# clockWiring.net
KiCad netlist of a schematic drawn in EAGLE
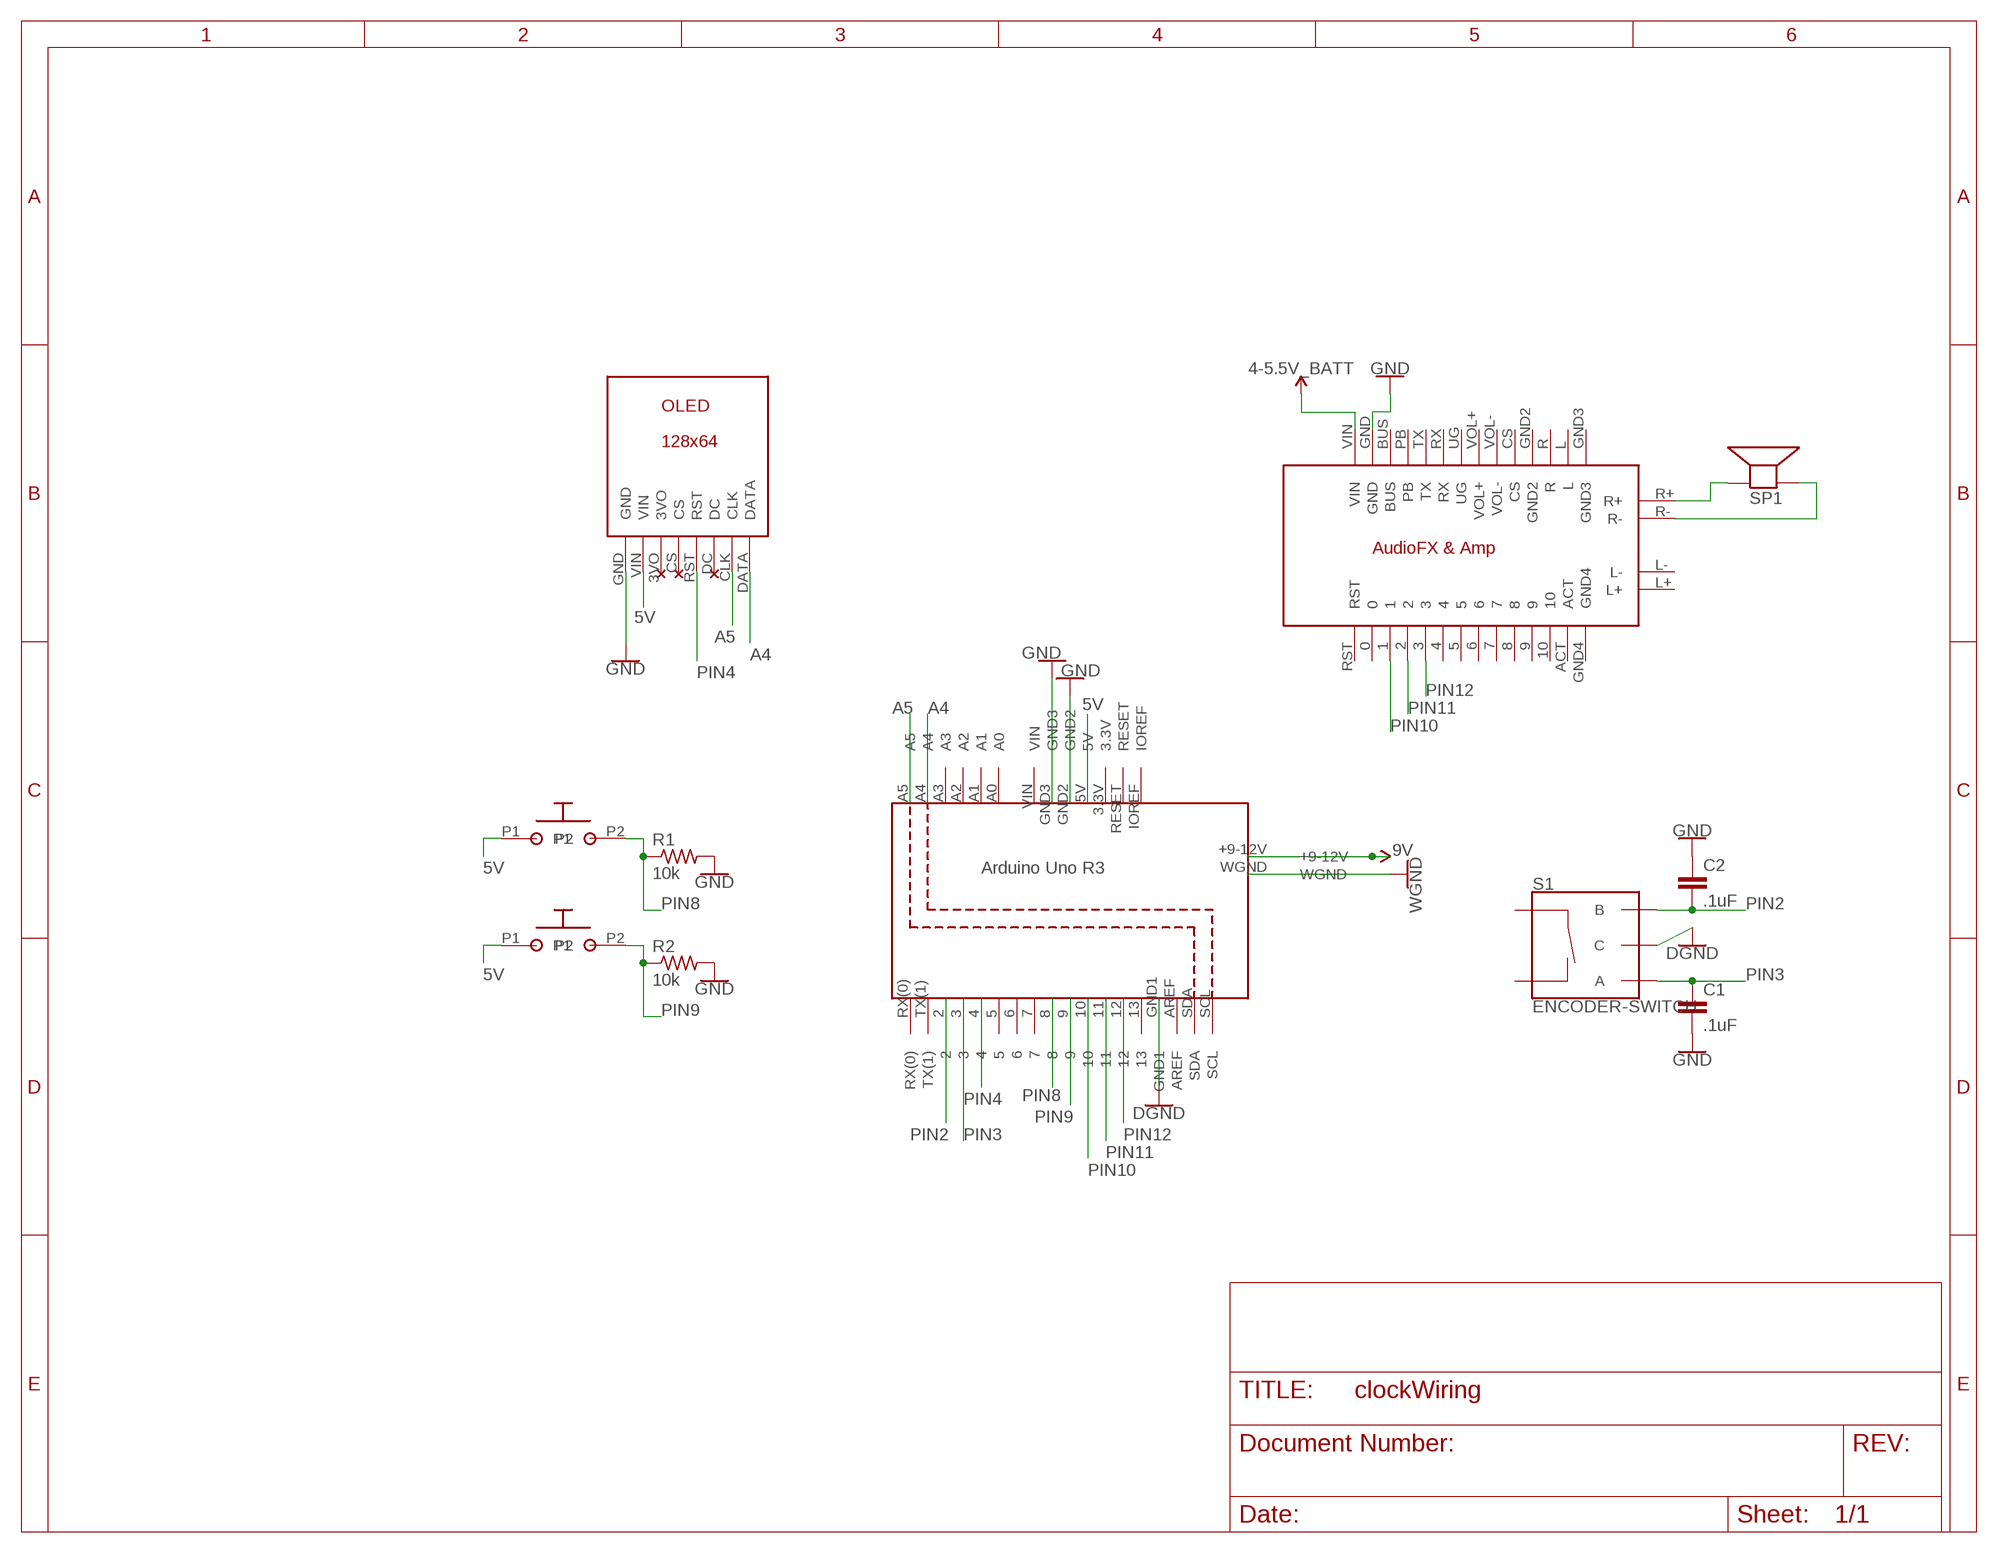
[diagram p0: schematic, sheet 1]

(export (version "E")
  (design (tool "Eeschema 10.0.6"))
  (components
    (comp (ref "C1")
      (value ".1uF")
      (footprint "eagle-import:C2.5-2")
      (libsource (lib "eagle-import") (part "C2.5/2"))
    )
    (comp (ref "C2")
      (value ".1uF")
      (footprint "eagle-import:C2.5-2")
      (libsource (lib "eagle-import") (part "C2.5/2"))
    )
    (comp (ref "R1")
      (value "10k")
      (footprint "eagle-import:0805-THM")
      (libsource (lib "eagle-import") (part "FLIPFLOP-RES"))
    )
    (comp (ref "R2")
      (value "10k")
      (footprint "eagle-import:0805-THM")
      (libsource (lib "eagle-import") (part "FLIPFLOP-RES"))
    )
    (comp (ref "S1")
      (value "ENCODER-SWITCH")
      (footprint "eagle-import:ROTARY_ENC_PLAIN")
      (libsource (lib "eagle-import") (part "ENCODER-SWITCH"))
    )
    (comp (ref "SP1")
      (value "SPEAKER/PS12")
      (footprint "eagle-import:PS12")
      (libsource (lib "eagle-import") (part "SPEAKER/PS12"))
    )
    (comp (ref "U$2")
      (value "OLED_128X64")
      (footprint "eagle-import:OLED_128X64")
      (libsource (lib "eagle-import") (part "OLED_128X64"))
    )
    (comp (ref "U$5")
      (value "AUDIOFX&AMP")
      (footprint "eagle-import:AUDIOFX&AMP")
      (libsource (lib "eagle-import") (part "AUDIOFX&AMP"))
    )
    (comp (ref "U$6")
      (value "ARDUINO_UNO")
      (footprint "eagle-import:ARDUINO_UNO")
      (libsource (lib "eagle-import") (part "ARDUINO_UNO"))
    )
    (comp (ref "U$7")
      (value "TWOPINBUTTON")
      (footprint "eagle-import:TWOPINBUTTON")
      (libsource (lib "eagle-import") (part "TWOPINBUTTON"))
    )
    (comp (ref "U$8")
      (value "TWOPINBUTTON")
      (footprint "eagle-import:TWOPINBUTTON")
      (libsource (lib "eagle-import") (part "TWOPINBUTTON"))
    )
  )
  (nets
    (net (code "1") (name "/5V") (class "Default")
      (node (ref "U$2") (pin "VIN") (pinfunction "VIN_VIN") (pintype "bidirectional"))
      (node (ref "U$6") (pin "5V") (pinfunction "5V_5V") (pintype "bidirectional"))
      (node (ref "U$7") (pin "P1") (pinfunction "P1_P1") (pintype "bidirectional"))
      (node (ref "U$8") (pin "P1") (pinfunction "P1_P1") (pintype "bidirectional"))
    )
    (net (code "2") (name "/A4") (class "Default")
      (node (ref "U$2") (pin "DATA") (pinfunction "DATA_DATA") (pintype "bidirectional"))
      (node (ref "U$6") (pin "A4") (pinfunction "A4_A4") (pintype "bidirectional"))
    )
    (net (code "3") (name "/A5") (class "Default")
      (node (ref "U$2") (pin "CLK") (pinfunction "CLK_CLK") (pintype "bidirectional"))
      (node (ref "U$6") (pin "A5") (pinfunction "A5_A5") (pintype "bidirectional"))
    )
    (net (code "4") (name "/PIN2") (class "Default")
      (node (ref "C2") (pin "2") (pinfunction "2_2") (pintype "passive"))
      (node (ref "S1") (pin "B") (pinfunction "B_B") (pintype "bidirectional"))
      (node (ref "U$6") (pin "2") (pinfunction "2_2") (pintype "bidirectional"))
    )
    (net (code "5") (name "/PIN3") (class "Default")
      (node (ref "C1") (pin "1") (pinfunction "1_1") (pintype "passive"))
      (node (ref "S1") (pin "A") (pinfunction "A_A") (pintype "bidirectional"))
      (node (ref "U$6") (pin "3") (pinfunction "3_3") (pintype "bidirectional"))
    )
    (net (code "6") (name "/PIN4") (class "Default")
      (node (ref "U$2") (pin "RST") (pinfunction "RST_RST") (pintype "bidirectional"))
      (node (ref "U$6") (pin "4") (pinfunction "4_4") (pintype "bidirectional"))
    )
    (net (code "7") (name "/PIN8") (class "Default")
      (node (ref "R1") (pin "1") (pinfunction "1_1") (pintype "passive"))
      (node (ref "U$6") (pin "8") (pinfunction "8_8") (pintype "bidirectional"))
      (node (ref "U$7") (pin "P2") (pinfunction "P2_P2") (pintype "bidirectional"))
    )
    (net (code "8") (name "/PIN9") (class "Default")
      (node (ref "R2") (pin "1") (pinfunction "1_1") (pintype "passive"))
      (node (ref "U$6") (pin "9") (pinfunction "9_9") (pintype "bidirectional"))
      (node (ref "U$8") (pin "P2") (pinfunction "P2_P2") (pintype "bidirectional"))
    )
    (net (code "9") (name "/PIN10") (class "Default")
      (node (ref "U$5") (pin "1") (pinfunction "1_1") (pintype "bidirectional"))
      (node (ref "U$6") (pin "10") (pinfunction "10_10") (pintype "bidirectional"))
    )
    (net (code "10") (name "/PIN11") (class "Default")
      (node (ref "U$5") (pin "2") (pinfunction "2_2") (pintype "bidirectional"))
      (node (ref "U$6") (pin "11") (pinfunction "11_11") (pintype "bidirectional"))
    )
    (net (code "11") (name "/PIN12") (class "Default")
      (node (ref "U$5") (pin "3") (pinfunction "3_3") (pintype "bidirectional"))
      (node (ref "U$6") (pin "12") (pinfunction "12_12") (pintype "bidirectional"))
    )
    (net (code "12") (name "4-5.5V_BATT") (class "Default")
      (node (ref "U$5") (pin "VIN") (pinfunction "VIN_VIN") (pintype "bidirectional"))
    )
    (net (code "13") (name "9V") (class "Default")
      (node (ref "U$6") (pin "+9-12V") (pinfunction "+9-12V_+9-12V") (pintype "bidirectional"))
    )
    (net (code "14") (name "DGND") (class "Default")
      (node (ref "C1") (pin "2") (pinfunction "2_2") (pintype "passive"))
      (node (ref "C2") (pin "1") (pinfunction "1_1") (pintype "passive"))
      (node (ref "R1") (pin "2") (pinfunction "2_2") (pintype "passive"))
      (node (ref "R2") (pin "2") (pinfunction "2_2") (pintype "passive"))
      (node (ref "S1") (pin "C") (pinfunction "C_C") (pintype "bidirectional"))
      (node (ref "U$2") (pin "GND") (pinfunction "GND_GND") (pintype "bidirectional"))
      (node (ref "U$5") (pin "GND") (pinfunction "GND_GND") (pintype "bidirectional"))
      (node (ref "U$6") (pin "GND1") (pinfunction "GND1_GND1") (pintype "bidirectional"))
      (node (ref "U$6") (pin "GND2") (pinfunction "GND2_GND2") (pintype "bidirectional"))
      (node (ref "U$6") (pin "GND3") (pinfunction "GND3_GND3") (pintype "bidirectional"))
      (node (ref "U$6") (pin "WGND") (pinfunction "WGND_WGND") (pintype "bidirectional"))
    )
    (net (code "15") (name "Net-(SP1-+)") (class "Default")
      (node (ref "SP1") (pin "P$1") (pinfunction "+_P$1") (pintype "passive"))
      (node (ref "U$5") (pin "R+") (pinfunction "R+_R+") (pintype "bidirectional"))
    )
    (net (code "16") (name "Net-(SP1--)") (class "Default")
      (node (ref "SP1") (pin "P$2") (pinfunction "-_P$2") (pintype "passive"))
      (node (ref "U$5") (pin "R-") (pinfunction "R-_R-") (pintype "bidirectional"))
    )
    (net (code "17") (name "unconnected-(S1-PadSW+)") (class "Default")
      (node (ref "S1") (pin "SW+") (pinfunction "SW+_SW+") (pintype "bidirectional"))
    )
    (net (code "18") (name "unconnected-(S1-PadSW-)") (class "Default")
      (node (ref "S1") (pin "SW-") (pinfunction "SW-_SW-") (pintype "bidirectional"))
    )
    (net (code "19") (name "unconnected-(U$2-Pad3VO)") (class "Default")
      (node (ref "U$2") (pin "3VO") (pinfunction "3VO_3VO") (pintype "bidirectional"))
    )
    (net (code "20") (name "unconnected-(U$2-PadCS)") (class "Default")
      (node (ref "U$2") (pin "CS") (pinfunction "CS_CS") (pintype "bidirectional"))
    )
    (net (code "21") (name "unconnected-(U$2-PadDC)") (class "Default")
      (node (ref "U$2") (pin "DC") (pinfunction "DC_DC") (pintype "bidirectional"))
    )
    (net (code "22") (name "unconnected-(U$5-Pad0)") (class "Default")
      (node (ref "U$5") (pin "0") (pinfunction "0_0") (pintype "bidirectional"))
    )
    (net (code "23") (name "unconnected-(U$5-Pad4)") (class "Default")
      (node (ref "U$5") (pin "4") (pinfunction "4_4") (pintype "bidirectional"))
    )
    (net (code "24") (name "unconnected-(U$5-Pad5)") (class "Default")
      (node (ref "U$5") (pin "5") (pinfunction "5_5") (pintype "bidirectional"))
    )
    (net (code "25") (name "unconnected-(U$5-Pad6)") (class "Default")
      (node (ref "U$5") (pin "6") (pinfunction "6_6") (pintype "bidirectional"))
    )
    (net (code "26") (name "unconnected-(U$5-Pad7)") (class "Default")
      (node (ref "U$5") (pin "7") (pinfunction "7_7") (pintype "bidirectional"))
    )
    (net (code "27") (name "unconnected-(U$5-Pad8)") (class "Default")
      (node (ref "U$5") (pin "8") (pinfunction "8_8") (pintype "bidirectional"))
    )
    (net (code "28") (name "unconnected-(U$5-Pad9)") (class "Default")
      (node (ref "U$5") (pin "9") (pinfunction "9_9") (pintype "bidirectional"))
    )
    (net (code "29") (name "unconnected-(U$5-Pad10)") (class "Default")
      (node (ref "U$5") (pin "10") (pinfunction "10_10") (pintype "bidirectional"))
    )
    (net (code "30") (name "unconnected-(U$5-PadACT)") (class "Default")
      (node (ref "U$5") (pin "ACT") (pinfunction "ACT_ACT") (pintype "bidirectional"))
    )
    (net (code "31") (name "unconnected-(U$5-PadBUS)") (class "Default")
      (node (ref "U$5") (pin "BUS") (pinfunction "BUS_BUS") (pintype "bidirectional"))
    )
    (net (code "32") (name "unconnected-(U$5-PadCS)") (class "Default")
      (node (ref "U$5") (pin "CS") (pinfunction "CS_CS") (pintype "bidirectional"))
    )
    (net (code "33") (name "unconnected-(U$5-PadGND2)") (class "Default")
      (node (ref "U$5") (pin "GND2") (pinfunction "GND2_GND2") (pintype "bidirectional"))
    )
    (net (code "34") (name "unconnected-(U$5-PadGND3)") (class "Default")
      (node (ref "U$5") (pin "GND3") (pinfunction "GND3_GND3") (pintype "bidirectional"))
    )
    (net (code "35") (name "unconnected-(U$5-PadGND4)") (class "Default")
      (node (ref "U$5") (pin "GND4") (pinfunction "GND4_GND4") (pintype "bidirectional"))
    )
    (net (code "36") (name "unconnected-(U$5-PadL)") (class "Default")
      (node (ref "U$5") (pin "L") (pinfunction "L_L") (pintype "bidirectional"))
    )
    (net (code "37") (name "unconnected-(U$5-PadL+)") (class "Default")
      (node (ref "U$5") (pin "L+") (pinfunction "L+_L+") (pintype "bidirectional"))
    )
    (net (code "38") (name "unconnected-(U$5-PadL-)") (class "Default")
      (node (ref "U$5") (pin "L-") (pinfunction "L-_L-") (pintype "bidirectional"))
    )
    (net (code "39") (name "unconnected-(U$5-PadPB)") (class "Default")
      (node (ref "U$5") (pin "PB") (pinfunction "PB_PB") (pintype "bidirectional"))
    )
    (net (code "40") (name "unconnected-(U$5-PadR)") (class "Default")
      (node (ref "U$5") (pin "R") (pinfunction "R_R") (pintype "bidirectional"))
    )
    (net (code "41") (name "unconnected-(U$5-PadRST)") (class "Default")
      (node (ref "U$5") (pin "RST") (pinfunction "RST_RST") (pintype "bidirectional"))
    )
    (net (code "42") (name "unconnected-(U$5-PadRX)") (class "Default")
      (node (ref "U$5") (pin "RX") (pinfunction "RX_RX") (pintype "bidirectional"))
    )
    (net (code "43") (name "unconnected-(U$5-PadTX)") (class "Default")
      (node (ref "U$5") (pin "TX") (pinfunction "TX_TX") (pintype "bidirectional"))
    )
    (net (code "44") (name "unconnected-(U$5-PadUG)") (class "Default")
      (node (ref "U$5") (pin "UG") (pinfunction "UG_UG") (pintype "bidirectional"))
    )
    (net (code "45") (name "unconnected-(U$5-PadVOL+)") (class "Default")
      (node (ref "U$5") (pin "VOL+") (pinfunction "VOL+_VOL+") (pintype "bidirectional"))
    )
    (net (code "46") (name "unconnected-(U$5-PadVOL-)") (class "Default")
      (node (ref "U$5") (pin "VOL-") (pinfunction "VOL-_VOL-") (pintype "bidirectional"))
    )
    (net (code "47") (name "unconnected-(U$6-Pad3.3V)") (class "Default")
      (node (ref "U$6") (pin "3.3V") (pinfunction "3.3V_3.3V") (pintype "bidirectional"))
    )
    (net (code "48") (name "unconnected-(U$6-Pad5)") (class "Default")
      (node (ref "U$6") (pin "5") (pinfunction "5_5") (pintype "bidirectional"))
    )
    (net (code "49") (name "unconnected-(U$6-Pad6)") (class "Default")
      (node (ref "U$6") (pin "6") (pinfunction "6_6") (pintype "bidirectional"))
    )
    (net (code "50") (name "unconnected-(U$6-Pad7)") (class "Default")
      (node (ref "U$6") (pin "7") (pinfunction "7_7") (pintype "bidirectional"))
    )
    (net (code "51") (name "unconnected-(U$6-Pad13)") (class "Default")
      (node (ref "U$6") (pin "13") (pinfunction "13_13") (pintype "bidirectional"))
    )
    (net (code "52") (name "unconnected-(U$6-PadA0)") (class "Default")
      (node (ref "U$6") (pin "A0") (pinfunction "A0_A0") (pintype "bidirectional"))
    )
    (net (code "53") (name "unconnected-(U$6-PadA1)") (class "Default")
      (node (ref "U$6") (pin "A1") (pinfunction "A1_A1") (pintype "bidirectional"))
    )
    (net (code "54") (name "unconnected-(U$6-PadA2)") (class "Default")
      (node (ref "U$6") (pin "A2") (pinfunction "A2_A2") (pintype "bidirectional"))
    )
    (net (code "55") (name "unconnected-(U$6-PadA3)") (class "Default")
      (node (ref "U$6") (pin "A3") (pinfunction "A3_A3") (pintype "bidirectional"))
    )
    (net (code "56") (name "unconnected-(U$6-PadAREF)") (class "Default")
      (node (ref "U$6") (pin "AREF") (pinfunction "AREF_AREF") (pintype "bidirectional"))
    )
    (net (code "57") (name "unconnected-(U$6-PadIOREF)") (class "Default")
      (node (ref "U$6") (pin "IOREF") (pinfunction "IOREF_IOREF") (pintype "bidirectional"))
    )
    (net (code "58") (name "unconnected-(U$6-PadRESET)") (class "Default")
      (node (ref "U$6") (pin "RESET") (pinfunction "RESET_RESET") (pintype "bidirectional"))
    )
    (net (code "59") (name "unconnected-(U$6-PadRX(0))") (class "Default")
      (node (ref "U$6") (pin "RX(0)") (pinfunction "RX(0)_RX(0)") (pintype "bidirectional"))
    )
    (net (code "60") (name "unconnected-(U$6-PadSCL)") (class "Default")
      (node (ref "U$6") (pin "SCL") (pinfunction "SCL_SCL") (pintype "bidirectional"))
    )
    (net (code "61") (name "unconnected-(U$6-PadSDA)") (class "Default")
      (node (ref "U$6") (pin "SDA") (pinfunction "SDA_SDA") (pintype "bidirectional"))
    )
    (net (code "62") (name "unconnected-(U$6-PadTX(1))") (class "Default")
      (node (ref "U$6") (pin "TX(1)") (pinfunction "TX(1)_TX(1)") (pintype "bidirectional"))
    )
    (net (code "63") (name "unconnected-(U$6-PadVIN)") (class "Default")
      (node (ref "U$6") (pin "VIN") (pinfunction "VIN_VIN") (pintype "bidirectional"))
    )
  )
)
